# Servo8_BKP.net
KiCad netlist of a schematic drawn in EAGLE
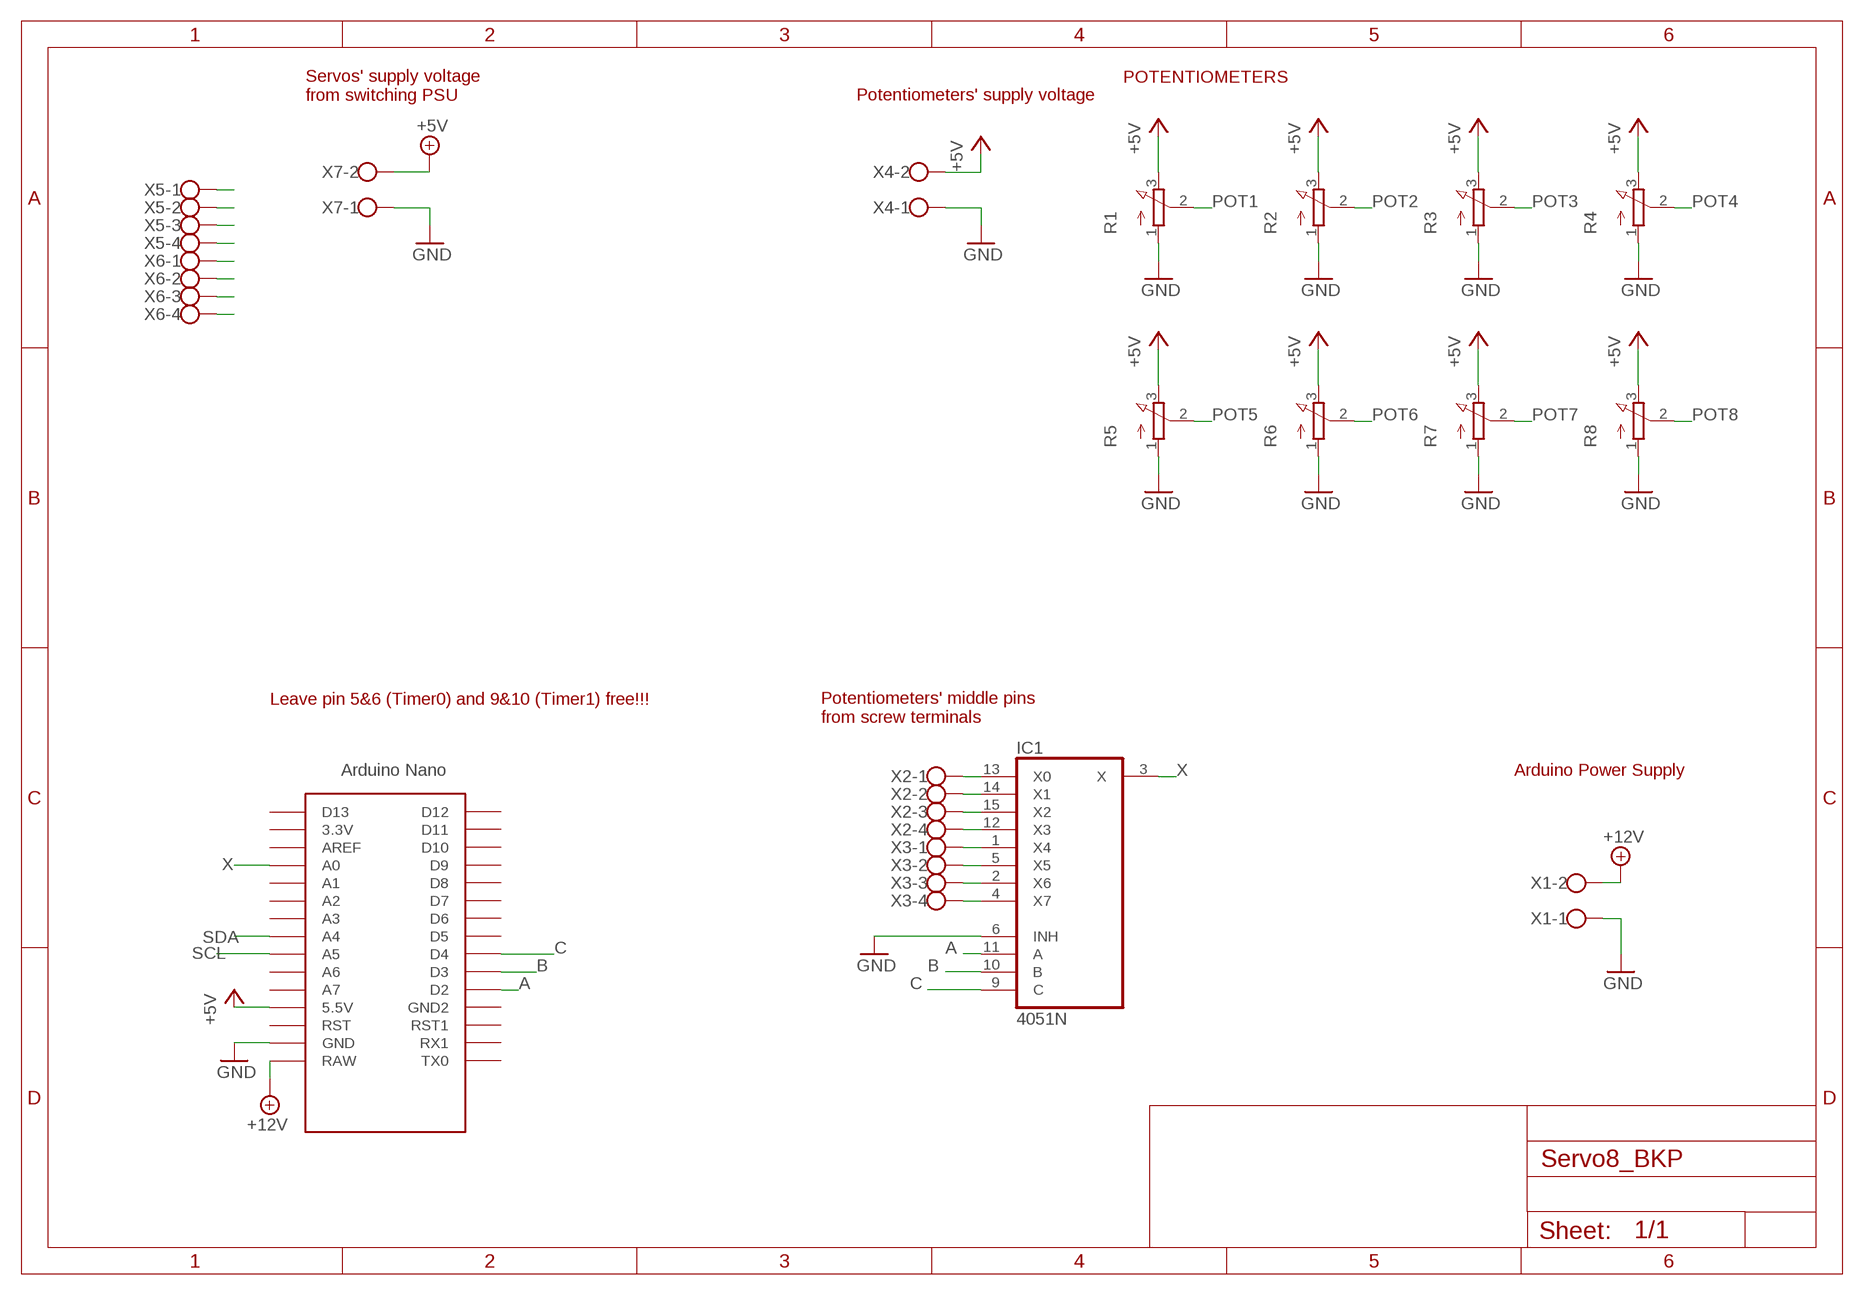
[diagram p0: schematic, sheet 1]

(export (version "E")
  (design (tool "Eeschema 10.0.6"))
  (components
    (comp (ref "IC1")
      (value "4051N")
      (footprint "eagle-import:DIL16")
      (libsource (lib "eagle-import") (part "4051N"))
    )
    (comp (ref "R1")
      (value "3RP/1610N")
      (footprint "eagle-import:3RP_1610N")
      (libsource (lib "eagle-import") (part "3RP/1610N"))
    )
    (comp (ref "R2")
      (value "3RP/1610N")
      (footprint "eagle-import:3RP_1610N")
      (libsource (lib "eagle-import") (part "3RP/1610N"))
    )
    (comp (ref "R3")
      (value "3RP/1610N")
      (footprint "eagle-import:3RP_1610N")
      (libsource (lib "eagle-import") (part "3RP/1610N"))
    )
    (comp (ref "R4")
      (value "3RP/1610N")
      (footprint "eagle-import:3RP_1610N")
      (libsource (lib "eagle-import") (part "3RP/1610N"))
    )
    (comp (ref "R5")
      (value "3RP/1610N")
      (footprint "eagle-import:3RP_1610N")
      (libsource (lib "eagle-import") (part "3RP/1610N"))
    )
    (comp (ref "R6")
      (value "3RP/1610N")
      (footprint "eagle-import:3RP_1610N")
      (libsource (lib "eagle-import") (part "3RP/1610N"))
    )
    (comp (ref "R7")
      (value "3RP/1610N")
      (footprint "eagle-import:3RP_1610N")
      (libsource (lib "eagle-import") (part "3RP/1610N"))
    )
    (comp (ref "R8")
      (value "3RP/1610N")
      (footprint "eagle-import:3RP_1610N")
      (libsource (lib "eagle-import") (part "3RP/1610N"))
    )
    (comp (ref "U$1")
      (value "NANO")
      (footprint "eagle-import:NANO")
      (libsource (lib "eagle-import") (part "NANO"))
    )
    (comp (ref "X1")
      (value "W237-102")
      (footprint "eagle-import:W237-102")
      (fields (field (name "MPN") "237-102"))
      (libsource (lib "eagle-import") (part "W237-102"))
    )
    (comp (ref "X2")
      (value "W237-4")
      (footprint "eagle-import:W237-4")
      (libsource (lib "eagle-import") (part "W237-4"))
    )
    (comp (ref "X3")
      (value "W237-4")
      (footprint "eagle-import:W237-4")
      (libsource (lib "eagle-import") (part "W237-4"))
    )
    (comp (ref "X4")
      (value "W237-102")
      (footprint "eagle-import:W237-102")
      (fields (field (name "MPN") "237-102"))
      (libsource (lib "eagle-import") (part "W237-102"))
    )
    (comp (ref "X5")
      (value "W237-4")
      (footprint "eagle-import:W237-4")
      (libsource (lib "eagle-import") (part "W237-4"))
    )
    (comp (ref "X6")
      (value "W237-4")
      (footprint "eagle-import:W237-4")
      (libsource (lib "eagle-import") (part "W237-4"))
    )
    (comp (ref "X7")
      (value "W237-102")
      (footprint "eagle-import:W237-102")
      (fields (field (name "MPN") "237-102"))
      (libsource (lib "eagle-import") (part "W237-102"))
    )
  )
  (nets
    (net (code "1") (name "+5V") (class "Default")
      (node (ref "R1") (pin "3") (pinfunction "E_3") (pintype "passive"))
      (node (ref "R2") (pin "3") (pinfunction "E_3") (pintype "passive"))
      (node (ref "R3") (pin "3") (pinfunction "E_3") (pintype "passive"))
      (node (ref "R4") (pin "3") (pinfunction "E_3") (pintype "passive"))
      (node (ref "R5") (pin "3") (pinfunction "E_3") (pintype "passive"))
      (node (ref "R6") (pin "3") (pinfunction "E_3") (pintype "passive"))
      (node (ref "R7") (pin "3") (pinfunction "E_3") (pintype "passive"))
      (node (ref "R8") (pin "3") (pinfunction "E_3") (pintype "passive"))
      (node (ref "U$1") (pin "5V") (pinfunction "5.5V_5V") (pintype "bidirectional"))
      (node (ref "X4") (pin "2") (pinfunction "KL_2") (pintype "passive"))
      (node (ref "X7") (pin "2") (pinfunction "KL_2") (pintype "passive"))
    )
    (net (code "2") (name "+12V") (class "Default")
      (node (ref "U$1") (pin "RAW") (pinfunction "RAW_RAW") (pintype "bidirectional"))
      (node (ref "X1") (pin "2") (pinfunction "KL_2") (pintype "passive"))
    )
    (net (code "3") (name "/A") (class "Default")
      (node (ref "IC1") (pin "11") (pinfunction "A_11") (pintype "input"))
      (node (ref "U$1") (pin "D2") (pinfunction "D2_D2") (pintype "bidirectional"))
    )
    (net (code "4") (name "/B") (class "Default")
      (node (ref "IC1") (pin "10") (pinfunction "B_10") (pintype "input"))
      (node (ref "U$1") (pin "D3") (pinfunction "D3_D3") (pintype "bidirectional"))
    )
    (net (code "5") (name "/C") (class "Default")
      (node (ref "IC1") (pin "9") (pinfunction "C_9") (pintype "input"))
      (node (ref "U$1") (pin "D4") (pinfunction "D4_D4") (pintype "bidirectional"))
    )
    (net (code "6") (name "/POT1") (class "Default")
      (node (ref "IC1") (pin "13") (pinfunction "X0_13") (pintype "bidirectional"))
      (node (ref "R1") (pin "2") (pinfunction "S_2") (pintype "passive"))
      (node (ref "X2") (pin "1") (pinfunction "KL_1") (pintype "passive"))
    )
    (net (code "7") (name "/POT2") (class "Default")
      (node (ref "IC1") (pin "14") (pinfunction "X1_14") (pintype "bidirectional"))
      (node (ref "R2") (pin "2") (pinfunction "S_2") (pintype "passive"))
      (node (ref "X2") (pin "2") (pinfunction "KL_2") (pintype "passive"))
    )
    (net (code "8") (name "/POT3") (class "Default")
      (node (ref "IC1") (pin "15") (pinfunction "X2_15") (pintype "bidirectional"))
      (node (ref "R3") (pin "2") (pinfunction "S_2") (pintype "passive"))
      (node (ref "X2") (pin "3") (pinfunction "KL_3") (pintype "passive"))
    )
    (net (code "9") (name "/POT4") (class "Default")
      (node (ref "IC1") (pin "12") (pinfunction "X3_12") (pintype "bidirectional"))
      (node (ref "R4") (pin "2") (pinfunction "S_2") (pintype "passive"))
      (node (ref "X2") (pin "4") (pinfunction "KL_4") (pintype "passive"))
    )
    (net (code "10") (name "/POT5") (class "Default")
      (node (ref "IC1") (pin "1") (pinfunction "X4_1") (pintype "bidirectional"))
      (node (ref "R5") (pin "2") (pinfunction "S_2") (pintype "passive"))
      (node (ref "X3") (pin "1") (pinfunction "KL_1") (pintype "passive"))
    )
    (net (code "11") (name "/POT6") (class "Default")
      (node (ref "IC1") (pin "5") (pinfunction "X5_5") (pintype "bidirectional"))
      (node (ref "R6") (pin "2") (pinfunction "S_2") (pintype "passive"))
      (node (ref "X3") (pin "2") (pinfunction "KL_2") (pintype "passive"))
    )
    (net (code "12") (name "/POT7") (class "Default")
      (node (ref "IC1") (pin "2") (pinfunction "X6_2") (pintype "bidirectional"))
      (node (ref "R7") (pin "2") (pinfunction "S_2") (pintype "passive"))
      (node (ref "X3") (pin "3") (pinfunction "KL_3") (pintype "passive"))
    )
    (net (code "13") (name "/POT8") (class "Default")
      (node (ref "IC1") (pin "4") (pinfunction "X7_4") (pintype "bidirectional"))
      (node (ref "R8") (pin "2") (pinfunction "S_2") (pintype "passive"))
      (node (ref "X3") (pin "4") (pinfunction "KL_4") (pintype "passive"))
    )
    (net (code "14") (name "/SCL") (class "Default")
      (node (ref "U$1") (pin "A5") (pinfunction "A5_A5") (pintype "bidirectional"))
    )
    (net (code "15") (name "/SDA") (class "Default")
      (node (ref "U$1") (pin "A4") (pinfunction "A4_A4") (pintype "bidirectional"))
    )
    (net (code "16") (name "/X") (class "Default")
      (node (ref "IC1") (pin "3") (pinfunction "X_3") (pintype "bidirectional"))
      (node (ref "U$1") (pin "A0") (pinfunction "A0_A0") (pintype "bidirectional"))
    )
    (net (code "17") (name "GND") (class "Default")
      (node (ref "IC1") (pin "6") (pinfunction "INH_6") (pintype "input"))
      (node (ref "R1") (pin "1") (pinfunction "A_1") (pintype "passive"))
      (node (ref "R2") (pin "1") (pinfunction "A_1") (pintype "passive"))
      (node (ref "R3") (pin "1") (pinfunction "A_1") (pintype "passive"))
      (node (ref "R4") (pin "1") (pinfunction "A_1") (pintype "passive"))
      (node (ref "R5") (pin "1") (pinfunction "A_1") (pintype "passive"))
      (node (ref "R6") (pin "1") (pinfunction "A_1") (pintype "passive"))
      (node (ref "R7") (pin "1") (pinfunction "A_1") (pintype "passive"))
      (node (ref "R8") (pin "1") (pinfunction "A_1") (pintype "passive"))
      (node (ref "U$1") (pin "GND") (pinfunction "GND_GND") (pintype "bidirectional"))
      (node (ref "X1") (pin "1") (pinfunction "KL_1") (pintype "passive"))
      (node (ref "X4") (pin "1") (pinfunction "KL_1") (pintype "passive"))
      (node (ref "X7") (pin "1") (pinfunction "KL_1") (pintype "passive"))
    )
    (net (code "18") (name "unconnected-(U$1-GND2-PadGND1)") (class "Default")
      (node (ref "U$1") (pin "GND1") (pinfunction "GND2_GND1") (pintype "bidirectional"))
    )
    (net (code "19") (name "unconnected-(U$1-Pad3.3V)") (class "Default")
      (node (ref "U$1") (pin "3.3V") (pinfunction "3.3V_3.3V") (pintype "bidirectional"))
    )
    (net (code "20") (name "unconnected-(U$1-PadA1)") (class "Default")
      (node (ref "U$1") (pin "A1") (pinfunction "A1_A1") (pintype "bidirectional"))
    )
    (net (code "21") (name "unconnected-(U$1-PadA2)") (class "Default")
      (node (ref "U$1") (pin "A2") (pinfunction "A2_A2") (pintype "bidirectional"))
    )
    (net (code "22") (name "unconnected-(U$1-PadA3)") (class "Default")
      (node (ref "U$1") (pin "A3") (pinfunction "A3_A3") (pintype "bidirectional"))
    )
    (net (code "23") (name "unconnected-(U$1-PadA6)") (class "Default")
      (node (ref "U$1") (pin "A6") (pinfunction "A6_A6") (pintype "bidirectional"))
    )
    (net (code "24") (name "unconnected-(U$1-PadA7)") (class "Default")
      (node (ref "U$1") (pin "A7") (pinfunction "A7_A7") (pintype "bidirectional"))
    )
    (net (code "25") (name "unconnected-(U$1-PadAREF)") (class "Default")
      (node (ref "U$1") (pin "AREF") (pinfunction "AREF_AREF") (pintype "bidirectional"))
    )
    (net (code "26") (name "unconnected-(U$1-PadD5)") (class "Default")
      (node (ref "U$1") (pin "D5") (pinfunction "D5_D5") (pintype "bidirectional"))
    )
    (net (code "27") (name "unconnected-(U$1-PadD6)") (class "Default")
      (node (ref "U$1") (pin "D6") (pinfunction "D6_D6") (pintype "bidirectional"))
    )
    (net (code "28") (name "unconnected-(U$1-PadD7)") (class "Default")
      (node (ref "U$1") (pin "D7") (pinfunction "D7_D7") (pintype "bidirectional"))
    )
    (net (code "29") (name "unconnected-(U$1-PadD8)") (class "Default")
      (node (ref "U$1") (pin "D8") (pinfunction "D8_D8") (pintype "bidirectional"))
    )
    (net (code "30") (name "unconnected-(U$1-PadD9)") (class "Default")
      (node (ref "U$1") (pin "D9") (pinfunction "D9_D9") (pintype "bidirectional"))
    )
    (net (code "31") (name "unconnected-(U$1-PadD10)") (class "Default")
      (node (ref "U$1") (pin "D10") (pinfunction "D10_D10") (pintype "bidirectional"))
    )
    (net (code "32") (name "unconnected-(U$1-PadD11)") (class "Default")
      (node (ref "U$1") (pin "D11") (pinfunction "D11_D11") (pintype "bidirectional"))
    )
    (net (code "33") (name "unconnected-(U$1-PadD12)") (class "Default")
      (node (ref "U$1") (pin "D12") (pinfunction "D12_D12") (pintype "bidirectional"))
    )
    (net (code "34") (name "unconnected-(U$1-PadD13)") (class "Default")
      (node (ref "U$1") (pin "D13") (pinfunction "D13_D13") (pintype "bidirectional"))
    )
    (net (code "35") (name "unconnected-(U$1-PadICSP1)") (class "Default")
      (node (ref "U$1") (pin "ICSP1") (pinfunction "ICSP1_ICSP1") (pintype "bidirectional"))
    )
    (net (code "36") (name "unconnected-(U$1-PadICSP2)") (class "Default")
      (node (ref "U$1") (pin "ICSP2") (pinfunction "ICSP2_ICSP2") (pintype "bidirectional"))
    )
    (net (code "37") (name "unconnected-(U$1-PadICSP3)") (class "Default")
      (node (ref "U$1") (pin "ICSP3") (pinfunction "ICSP3_ICSP3") (pintype "bidirectional"))
    )
    (net (code "38") (name "unconnected-(U$1-PadICSP4)") (class "Default")
      (node (ref "U$1") (pin "ICSP4") (pinfunction "ICSP4_ICSP4") (pintype "bidirectional"))
    )
    (net (code "39") (name "unconnected-(U$1-PadICSP5)") (class "Default")
      (node (ref "U$1") (pin "ICSP5") (pinfunction "ICSP5_ICSP5") (pintype "bidirectional"))
    )
    (net (code "40") (name "unconnected-(U$1-PadICSP6)") (class "Default")
      (node (ref "U$1") (pin "ICSP6") (pinfunction "ICSP6_ICSP6") (pintype "bidirectional"))
    )
    (net (code "41") (name "unconnected-(U$1-PadRST)") (class "Default")
      (node (ref "U$1") (pin "RST") (pinfunction "RST_RST") (pintype "bidirectional"))
    )
    (net (code "42") (name "unconnected-(U$1-PadRST1)") (class "Default")
      (node (ref "U$1") (pin "RST1") (pinfunction "RST1_RST1") (pintype "bidirectional"))
    )
    (net (code "43") (name "unconnected-(U$1-PadRX1)") (class "Default")
      (node (ref "U$1") (pin "RX1") (pinfunction "RX1_RX1") (pintype "bidirectional"))
    )
    (net (code "44") (name "unconnected-(U$1-PadTX0)") (class "Default")
      (node (ref "U$1") (pin "TX0") (pinfunction "TX0_TX0") (pintype "bidirectional"))
    )
    (net (code "45") (name "unconnected-(X5A-KL-Pad1)") (class "Default")
      (node (ref "X5") (pin "1") (pinfunction "KL_1") (pintype "passive"))
    )
    (net (code "46") (name "unconnected-(X5B-KL-Pad2)") (class "Default")
      (node (ref "X5") (pin "2") (pinfunction "KL_2") (pintype "passive"))
    )
    (net (code "47") (name "unconnected-(X5C-KL-Pad3)") (class "Default")
      (node (ref "X5") (pin "3") (pinfunction "KL_3") (pintype "passive"))
    )
    (net (code "48") (name "unconnected-(X5D-KL-Pad4)") (class "Default")
      (node (ref "X5") (pin "4") (pinfunction "KL_4") (pintype "passive"))
    )
    (net (code "49") (name "unconnected-(X6A-KL-Pad1)") (class "Default")
      (node (ref "X6") (pin "1") (pinfunction "KL_1") (pintype "passive"))
    )
    (net (code "50") (name "unconnected-(X6B-KL-Pad2)") (class "Default")
      (node (ref "X6") (pin "2") (pinfunction "KL_2") (pintype "passive"))
    )
    (net (code "51") (name "unconnected-(X6C-KL-Pad3)") (class "Default")
      (node (ref "X6") (pin "3") (pinfunction "KL_3") (pintype "passive"))
    )
    (net (code "52") (name "unconnected-(X6D-KL-Pad4)") (class "Default")
      (node (ref "X6") (pin "4") (pinfunction "KL_4") (pintype "passive"))
    )
  )
)
